# tia2.net
KiCad netlist of a schematic drawn in Altium Designer
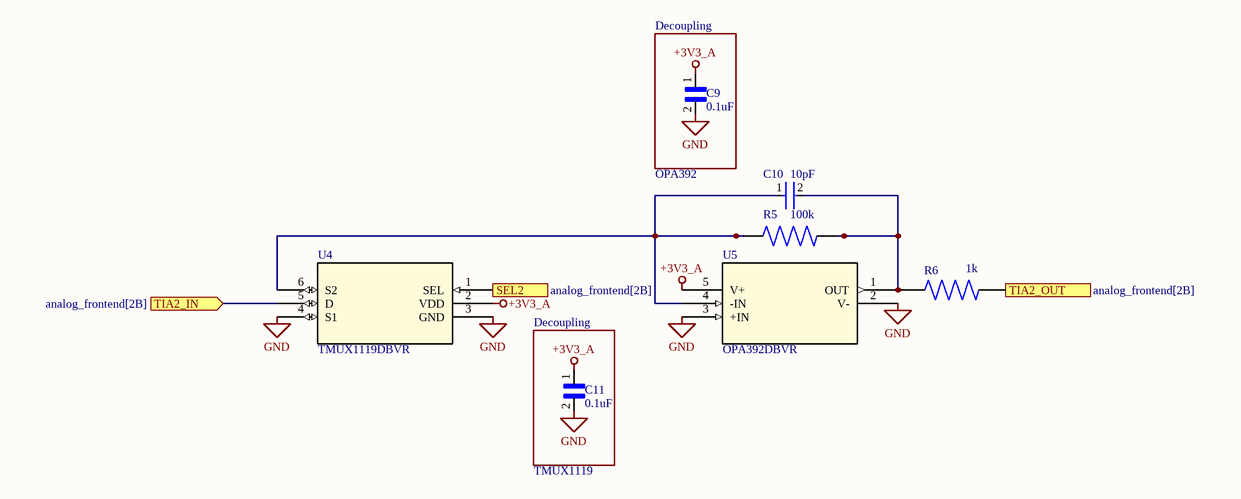
[diagram p0: tia2.SchDoc]

(export (version "E")
  (design (tool "Eeschema 10.0.6"))
  (components
    (comp (ref "C9")
      (value "0.1uF")
      (footprint "CC0603JRX7R8BB104")
      (description "25V 100nF X7R ±5% 0603 Multilayer Ceramic Capacitors MLCC - SMD/SMT ROHS")
      (fields
        (field (name "MANUFACTURER") "Yageo Group")
        (field (name "MANUFACTURER PART NUMBER") "CC0603JRX7R8BB104")
      )
      (libsource (lib "opm_lib") (part "CC0603JRX7R8BB104"))
    )
    (comp (ref "C10")
      (value "10pF")
      (footprint "GCM1885C2A100JA16D")
      (description "100V 10pF C0G ±5% 0603 Multilayer Ceramic Capacitors MLCC - SMD/SMT ROHS")
      (fields
        (field (name "MANUFACTURER") "Murata")
        (field (name "MANUFACTURER PART NUMBER") "GCM1885C2A100JA16D")
      )
      (libsource (lib "opm_lib") (part "GCM1885C2A100JA16D"))
    )
    (comp (ref "C11")
      (value "0.1uF")
      (footprint "CC0603JRX7R8BB104")
      (description "25V 100nF X7R ±5% 0603 Multilayer Ceramic Capacitors MLCC - SMD/SMT ROHS")
      (fields
        (field (name "MANUFACTURER") "Yageo Group")
        (field (name "MANUFACTURER PART NUMBER") "CC0603JRX7R8BB104")
      )
      (libsource (lib "opm_lib") (part "CC0603JRX7R8BB104"))
    )
    (comp (ref "R5")
      (value "100k")
      (footprint "RESC2012X55N")
      (description "Fixed Resistor, Thin Film, 0.125W, 100000ohm, 150V, 0.1% +/-Tol, 15ppm/Cel, Surface Mount, 0805")
      (fields
        (field (name "MANUFACTURER") "Vishay")
        (field (name "MANUFACTURER PART NUMBER") "TNPW0805100KBXEN")
      )
      (libsource (lib "opm_lib") (part "TNPW0805100KBXEN"))
    )
    (comp (ref "R6")
      (value "1k")
      (footprint "RESC1508X55N")
      (description "Fixed Resistor, Thin Film, 0.1W, 1000ohm, 75V, 0.1% +/-Tol, 15ppm/Cel, Surface Mount, 0603")
      (fields
        (field (name "MANUFACTURER") "Vishay")
        (field (name "MANUFACTURER PART NUMBER") "TNPW06031K00BXEN")
      )
      (libsource (lib "opm_lib") (part "TNPW06031K00BXEN"))
    )
    (comp (ref "U4")
      (value "TMUX1119DBVR")
      (footprint "TMUX1119DBVR")
      (fields (field (name "MANUFACTURER") "Texas Instruments"))
      (libsource (lib "opm_lib") (part "TMUX1119DBVR"))
    )
    (comp (ref "U5")
      (value "OPA392DBVR")
      (footprint "OPA392DBVR")
      (description "Operational Amplifier, 1 Func, 10uV Offset-Max, CMOS, PDSO5")
      (fields (field (name "MANUFACTURER") "Texas Instruments"))
      (libsource (lib "opm_lib") (part "OPA392DBVR"))
    )
  )
  (nets
    (net (code "1") (name "+3V3_A") (class "Default")
      (node (ref "C11") (pin "1") (pinfunction "1_1") (pintype "passive"))
      (node (ref "C9") (pin "1") (pinfunction "1_1") (pintype "passive"))
      (node (ref "U4") (pin "2") (pinfunction "VDD_2") (pintype "power_in"))
      (node (ref "U5") (pin "5") (pinfunction "V+_5") (pintype "power_in"))
    )
    (net (code "2") (name "/SEL2") (class "Default")
      (node (ref "U4") (pin "1") (pinfunction "SEL_1") (pintype "input"))
    )
    (net (code "3") (name "/TIA2_IN") (class "Default")
      (node (ref "U4") (pin "5") (pinfunction "D_5") (pintype "bidirectional"))
    )
    (net (code "4") (name "/TIA2_OUT") (class "Default")
      (node (ref "R6") (pin "2") (pinfunction "2_2") (pintype "passive"))
    )
    (net (code "5") (name "GND") (class "Default")
      (node (ref "C11") (pin "2") (pinfunction "2_2") (pintype "passive"))
      (node (ref "C9") (pin "2") (pinfunction "2_2") (pintype "passive"))
      (node (ref "U4") (pin "3") (pinfunction "GND_3") (pintype "power_in"))
      (node (ref "U4") (pin "4") (pinfunction "S1_4") (pintype "bidirectional"))
      (node (ref "U5") (pin "2") (pinfunction "V-_2") (pintype "power_in"))
      (node (ref "U5") (pin "3") (pinfunction "+IN_3") (pintype "input"))
    )
    (net (code "6") (name "Net-(U4-S2)") (class "Default")
      (node (ref "C10") (pin "1") (pinfunction "1_1") (pintype "passive"))
      (node (ref "R5") (pin "1") (pinfunction "1_1") (pintype "passive"))
      (node (ref "U4") (pin "6") (pinfunction "S2_6") (pintype "bidirectional"))
      (node (ref "U5") (pin "4") (pinfunction "-IN_4") (pintype "input"))
    )
    (net (code "7") (name "Net-(U5-OUT)") (class "Default")
      (node (ref "C10") (pin "2") (pinfunction "2_2") (pintype "passive"))
      (node (ref "R5") (pin "2") (pinfunction "2_2") (pintype "passive"))
      (node (ref "R6") (pin "1") (pinfunction "1_1") (pintype "passive"))
      (node (ref "U5") (pin "1") (pinfunction "OUT_1") (pintype "output"))
    )
  )
)
